# driver.net
KiCad netlist of a schematic drawn in Altium Designer
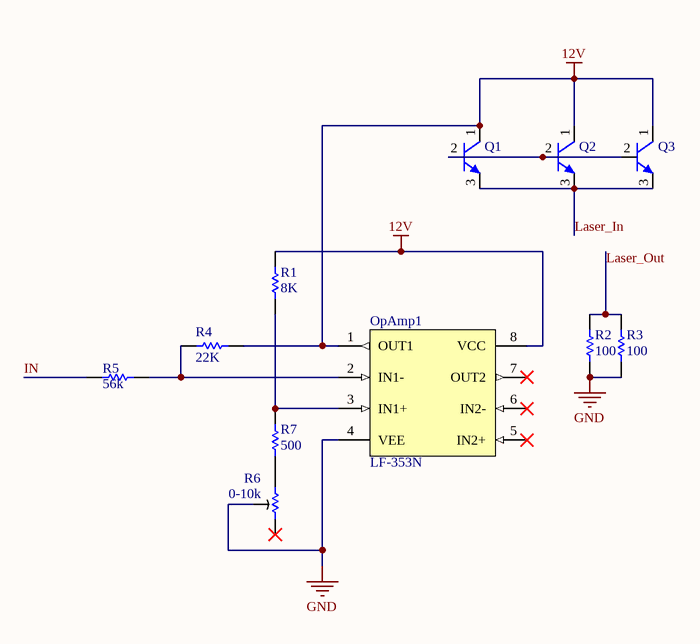
[diagram p0: driver.SchDoc]

(export (version "E")
  (design (tool "Eeschema 10.0.6"))
  (components
    (comp (ref "OpAmp1")
      (value "LF-353N")
      (footprint "6 pin socket")
      (libsource (lib "OpAmps") (part "LF353NFS-ND"))
    )
    (comp (ref "Q1")
      (value "~")
      (footprint "NPN socket")
      (description "NPN Bipolar Transistor")
      (libsource (lib "Transistor") (part "MMBT3904"))
    )
    (comp (ref "Q2")
      (value "~")
      (footprint "NPN socket")
      (description "NPN Bipolar Transistor")
      (libsource (lib "Transistor") (part "MMBT3904"))
    )
    (comp (ref "Q3")
      (value "~")
      (footprint "NPN socket")
      (description "NPN Bipolar Transistor")
      (libsource (lib "Transistor") (part "MMBT3904"))
    )
    (comp (ref "R1")
      (value "8K")
      (footprint "SMT 0805 (2012)")
      (description "Resistor 22K 1% Surface Mount 0804")
      (fields (field (name "POWER") "100 mW") (field (name "Comment") "Resistor 22K 0804"))
      (libsource (lib "Resistor") (part "Resistor 22K 0804"))
    )
    (comp (ref "R2")
      (value "100")
      (footprint "SMT 0805 (2012)")
      (description "Resistor 22K 1% Surface Mount 0804")
      (fields (field (name "POWER") "100 mW") (field (name "Comment") "Resistor 22K 0804"))
      (libsource (lib "Resistor") (part "Resistor 22K 0804"))
    )
    (comp (ref "R3")
      (value "100")
      (footprint "SMT 0805 (2012)")
      (description "Resistor 22K 1% Surface Mount 0804")
      (fields (field (name "POWER") "100 mW") (field (name "Comment") "Resistor 22K 0804"))
      (libsource (lib "Resistor") (part "Resistor 22K 0804"))
    )
    (comp (ref "R4")
      (value "22K")
      (footprint "SMT 0805 (2012)")
      (description "Resistor 22K 1% Surface Mount 0804")
      (fields (field (name "POWER") "100 mW") (field (name "Comment") "Resistor 22K 0804"))
      (libsource (lib "Resistor") (part "Resistor 22K 0804"))
    )
    (comp (ref "R5")
      (value "56k")
      (footprint "SMT 0805 (2012)")
      (description "Resistor 56K 0804")
      (fields (field (name "Comment") "Resistor 56K Ohm"))
      (libsource (lib "Resistor") (part "Resistor 56k Ohm 0804"))
    )
    (comp (ref "R6")
      (value "0-10k")
      (footprint "pot socket")
      (description "10K pot")
      (fields (field (name "POWER") "100 mW"))
      (libsource (lib "Resistor") (part "10K pot"))
    )
    (comp (ref "R7")
      (value "500")
      (footprint "SMT 0805 (2012)")
      (description "Resistor 22K 1% Surface Mount 0804")
      (fields (field (name "POWER") "100 mW") (field (name "Comment") "Resistor 500 0804"))
      (libsource (lib "Resistor") (part "Resistor 22K 0804"))
    )
  )
  (nets
    (net (code "1") (name "/IN") (class "Default")
      (node (ref "R5") (pin "2") (pinfunction "2_2") (pintype "passive"))
    )
    (net (code "2") (name "/Laser_In") (class "Default")
      (node (ref "Q1") (pin "3") (pinfunction "3_3") (pintype "passive"))
      (node (ref "Q2") (pin "3") (pinfunction "3_3") (pintype "passive"))
      (node (ref "Q3") (pin "3") (pinfunction "3_3") (pintype "passive"))
    )
    (net (code "3") (name "/Laser_Out") (class "Default")
      (node (ref "R2") (pin "1") (pinfunction "1_1") (pintype "passive"))
      (node (ref "R3") (pin "1") (pinfunction "1_1") (pintype "passive"))
    )
    (net (code "4") (name "12V") (class "Default")
      (node (ref "OpAmp1") (pin "1") (pinfunction "OUT1_1") (pintype "output"))
      (node (ref "OpAmp1") (pin "8") (pinfunction "VCC_8") (pintype "power_in"))
      (node (ref "Q1") (pin "1") (pinfunction "1_1") (pintype "passive"))
      (node (ref "Q2") (pin "1") (pinfunction "1_1") (pintype "passive"))
      (node (ref "Q3") (pin "1") (pinfunction "1_1") (pintype "passive"))
      (node (ref "R1") (pin "1") (pinfunction "1_1") (pintype "passive"))
      (node (ref "R4") (pin "2") (pinfunction "2_2") (pintype "passive"))
    )
    (net (code "5") (name "GND") (class "Default")
      (node (ref "OpAmp1") (pin "4") (pinfunction "VEE_4") (pintype "power_in"))
      (node (ref "R2") (pin "2") (pinfunction "2_2") (pintype "passive"))
      (node (ref "R3") (pin "2") (pinfunction "2_2") (pintype "passive"))
      (node (ref "R6") (pin "2") (pinfunction "2_2") (pintype "passive"))
    )
    (net (code "6") (name "Net-(OpAmp1-IN1+)") (class "Default")
      (node (ref "OpAmp1") (pin "3") (pinfunction "IN1+_3") (pintype "input"))
      (node (ref "R1") (pin "2") (pinfunction "2_2") (pintype "passive"))
      (node (ref "R7") (pin "1") (pinfunction "1_1") (pintype "passive"))
    )
    (net (code "7") (name "Net-(OpAmp1-IN1-)") (class "Default")
      (node (ref "OpAmp1") (pin "2") (pinfunction "IN1-_2") (pintype "input"))
      (node (ref "R4") (pin "1") (pinfunction "1_1") (pintype "passive"))
      (node (ref "R5") (pin "1") (pinfunction "1_1") (pintype "passive"))
    )
    (net (code "8") (name "Net-(Q1-Pad2)") (class "Default")
      (node (ref "Q1") (pin "2") (pinfunction "2_2") (pintype "passive"))
      (node (ref "Q2") (pin "2") (pinfunction "2_2") (pintype "passive"))
      (node (ref "Q3") (pin "2") (pinfunction "2_2") (pintype "passive"))
    )
    (net (code "9") (name "Net-(R6-Pad1)") (class "Default")
      (node (ref "R6") (pin "1") (pinfunction "1_1") (pintype "passive"))
      (node (ref "R7") (pin "2") (pinfunction "2_2") (pintype "passive"))
    )
    (net (code "10") (name "unconnected-(OpAmp1-IN2+-Pad5)") (class "Default")
      (node (ref "OpAmp1") (pin "5") (pinfunction "IN2+_5") (pintype "input+no_connect"))
    )
    (net (code "11") (name "unconnected-(OpAmp1-IN2--Pad6)") (class "Default")
      (node (ref "OpAmp1") (pin "6") (pinfunction "IN2-_6") (pintype "input+no_connect"))
    )
    (net (code "12") (name "unconnected-(OpAmp1-OUT2-Pad7)") (class "Default")
      (node (ref "OpAmp1") (pin "7") (pinfunction "OUT2_7") (pintype "output+no_connect"))
    )
    (net (code "13") (name "unconnected-(R6-Pad3)") (class "Default")
      (node (ref "R6") (pin "3") (pinfunction "3_3") (pintype "passive+no_connect"))
    )
  )
)
